# buttons_board.net
KiCad netlist of a schematic drawn in EAGLE
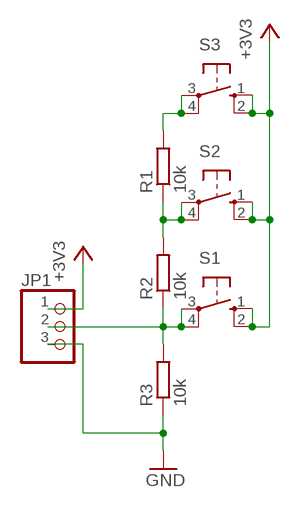
[diagram p0: schematic, sheet 1]

(export (version "E")
  (design (tool "Eeschema 10.0.6"))
  (components
    (comp (ref "JP1")
      (value "PINHD-1X3/90")
      (footprint "eagle-import:1X03_90")
      (libsource (lib "eagle-import") (part "PINHD-1X3/90"))
    )
    (comp (ref "R1")
      (value "10k")
      (footprint "eagle-import:R1206")
      (libsource (lib "eagle-import") (part "R-EU_R1206"))
    )
    (comp (ref "R2")
      (value "10k")
      (footprint "eagle-import:R1206")
      (libsource (lib "eagle-import") (part "R-EU_R1206"))
    )
    (comp (ref "R3")
      (value "10k")
      (footprint "eagle-import:R1206")
      (libsource (lib "eagle-import") (part "R-EU_R1206"))
    )
    (comp (ref "S1")
      (value "10-XX")
      (footprint "eagle-import:B3F-10XX")
      (fields (field (name "MPN") "B3F-1000"))
      (libsource (lib "eagle-import") (part "10-XX"))
    )
    (comp (ref "S2")
      (value "10-XX")
      (footprint "eagle-import:B3F-10XX")
      (fields (field (name "MPN") "B3F-1000"))
      (libsource (lib "eagle-import") (part "10-XX"))
    )
    (comp (ref "S3")
      (value "10-XX")
      (footprint "eagle-import:B3F-10XX")
      (fields (field (name "MPN") "B3F-1000"))
      (libsource (lib "eagle-import") (part "10-XX"))
    )
  )
  (nets
    (net (code "1") (name "+3V3") (class "Default")
      (node (ref "JP1") (pin "1") (pinfunction "1_1") (pintype "passive"))
      (node (ref "S1") (pin "1") (pinfunction "S_1") (pintype "passive"))
      (node (ref "S1") (pin "2") (pinfunction "S1_2") (pintype "passive"))
      (node (ref "S2") (pin "1") (pinfunction "S_1") (pintype "passive"))
      (node (ref "S2") (pin "2") (pinfunction "S1_2") (pintype "passive"))
      (node (ref "S3") (pin "1") (pinfunction "S_1") (pintype "passive"))
      (node (ref "S3") (pin "2") (pinfunction "S1_2") (pintype "passive"))
    )
    (net (code "2") (name "GND") (class "Default")
      (node (ref "JP1") (pin "3") (pinfunction "3_3") (pintype "passive"))
      (node (ref "R3") (pin "1") (pinfunction "1_1") (pintype "passive"))
    )
    (net (code "3") (name "Net-(S1-P)") (class "Default")
      (node (ref "JP1") (pin "2") (pinfunction "2_2") (pintype "passive"))
      (node (ref "R2") (pin "1") (pinfunction "1_1") (pintype "passive"))
      (node (ref "R3") (pin "2") (pinfunction "2_2") (pintype "passive"))
      (node (ref "S1") (pin "3") (pinfunction "P_3") (pintype "passive"))
      (node (ref "S1") (pin "4") (pinfunction "P1_4") (pintype "passive"))
    )
    (net (code "4") (name "Net-(S2-P)") (class "Default")
      (node (ref "R1") (pin "1") (pinfunction "1_1") (pintype "passive"))
      (node (ref "R2") (pin "2") (pinfunction "2_2") (pintype "passive"))
      (node (ref "S2") (pin "3") (pinfunction "P_3") (pintype "passive"))
      (node (ref "S2") (pin "4") (pinfunction "P1_4") (pintype "passive"))
    )
    (net (code "5") (name "Net-(S3-P)") (class "Default")
      (node (ref "R1") (pin "2") (pinfunction "2_2") (pintype "passive"))
      (node (ref "S3") (pin "3") (pinfunction "P_3") (pintype "passive"))
      (node (ref "S3") (pin "4") (pinfunction "P1_4") (pintype "passive"))
    )
  )
)
